# eagle_exp_1.net
KiCad netlist of a schematic drawn in EAGLE
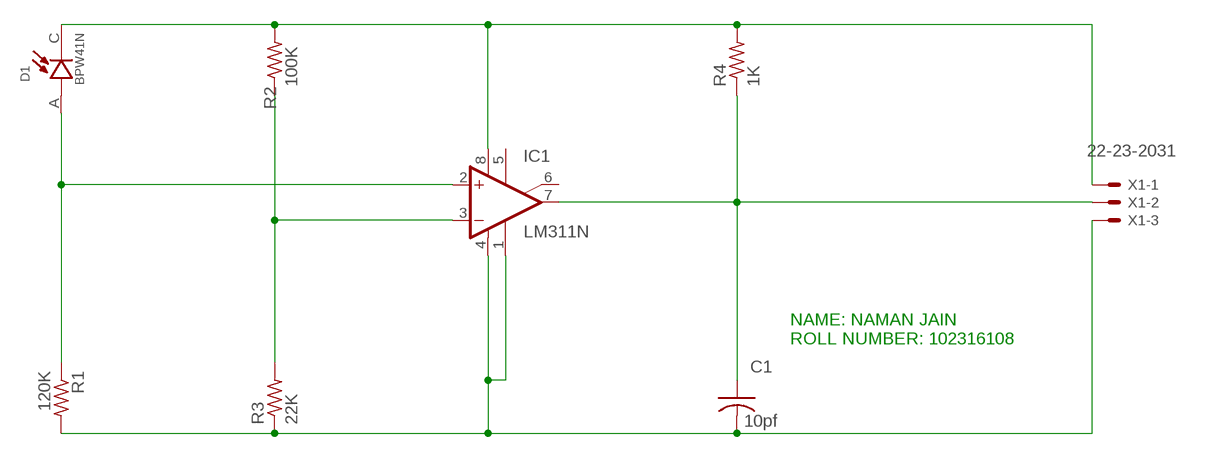
[diagram p0: schematic, sheet 1]

(export (version "E")
  (design (tool "Eeschema 10.0.6"))
  (components
    (comp (ref "C1")
      (value "10pf")
      (footprint "eagle-import:C025-024X044")
      (libsource (lib "eagle-import") (part "C-US025-024X044"))
    )
    (comp (ref "D1")
      (value "BPW41N")
      (footprint "eagle-import:DIO_BPW41N")
      (fields (field (name "MF") "Vishay Semiconductor Opto Division"))
      (libsource (lib "eagle-import") (part "BPW41N"))
    )
    (comp (ref "IC1")
      (value "LM311N")
      (footprint "eagle-import:DIL08")
      (libsource (lib "eagle-import") (part "LM311N"))
    )
    (comp (ref "R1")
      (value "120K")
      (footprint "eagle-import:0204_5")
      (libsource (lib "eagle-import") (part "R-US_0204/5"))
    )
    (comp (ref "R2")
      (value "100K")
      (footprint "eagle-import:0204_5")
      (libsource (lib "eagle-import") (part "R-US_0204/5"))
    )
    (comp (ref "R3")
      (value "22K")
      (footprint "eagle-import:0204_5")
      (libsource (lib "eagle-import") (part "R-US_0204/5"))
    )
    (comp (ref "R4")
      (value "1K")
      (footprint "eagle-import:0204_5")
      (libsource (lib "eagle-import") (part "R-US_0204/5"))
    )
    (comp (ref "X1")
      (value "22-23-2031")
      (footprint "eagle-import:22-23-2031")
      (fields (field (name "MF") "MOLEX"))
      (libsource (lib "eagle-import") (part "22-23-2031"))
    )
  )
  (nets
    (net (code "1") (name "Net-(IC1-+IN)") (class "Default")
      (node (ref "D1") (pin "A") (pinfunction "A_A") (pintype "passive"))
      (node (ref "IC1") (pin "2") (pinfunction "+IN_2") (pintype "input"))
      (node (ref "R1") (pin "1") (pinfunction "1_1") (pintype "passive"))
    )
    (net (code "2") (name "Net-(IC1--IN)") (class "Default")
      (node (ref "IC1") (pin "3") (pinfunction "-IN_3") (pintype "input"))
      (node (ref "R2") (pin "1") (pinfunction "1_1") (pintype "passive"))
      (node (ref "R3") (pin "2") (pinfunction "2_2") (pintype "passive"))
    )
    (net (code "3") (name "Net-(IC1-GND)") (class "Default")
      (node (ref "C1") (pin "2") (pinfunction "2_2") (pintype "passive"))
      (node (ref "IC1") (pin "1") (pinfunction "GND_1") (pintype "passive"))
      (node (ref "IC1") (pin "4") (pinfunction "V-_4") (pintype "power_in"))
      (node (ref "R1") (pin "2") (pinfunction "2_2") (pintype "passive"))
      (node (ref "R3") (pin "1") (pinfunction "1_1") (pintype "passive"))
      (node (ref "X1") (pin "3") (pinfunction "S_3") (pintype "passive"))
    )
    (net (code "4") (name "Net-(IC1-OUT)") (class "Default")
      (node (ref "C1") (pin "1") (pinfunction "1_1") (pintype "passive"))
      (node (ref "IC1") (pin "7") (pinfunction "OUT_7") (pintype "output"))
      (node (ref "R4") (pin "1") (pinfunction "1_1") (pintype "passive"))
      (node (ref "X1") (pin "2") (pinfunction "S_2") (pintype "passive"))
    )
    (net (code "5") (name "Net-(IC1-V+)") (class "Default")
      (node (ref "D1") (pin "C") (pinfunction "C_C") (pintype "passive"))
      (node (ref "IC1") (pin "8") (pinfunction "V+_8") (pintype "power_in"))
      (node (ref "R2") (pin "2") (pinfunction "2_2") (pintype "passive"))
      (node (ref "R4") (pin "2") (pinfunction "2_2") (pintype "passive"))
      (node (ref "X1") (pin "1") (pinfunction "S_1") (pintype "passive"))
    )
    (net (code "6") (name "unconnected-(IC1-ON-Pad5)") (class "Default")
      (node (ref "IC1") (pin "5") (pinfunction "ON_5") (pintype "passive"))
    )
    (net (code "7") (name "unconnected-(IC1-ON{slash}STR-Pad6)") (class "Default")
      (node (ref "IC1") (pin "6") (pinfunction "ON/STR_6") (pintype "passive"))
    )
  )
)
